# LSM303D.net
KiCad netlist of a schematic drawn in EAGLE
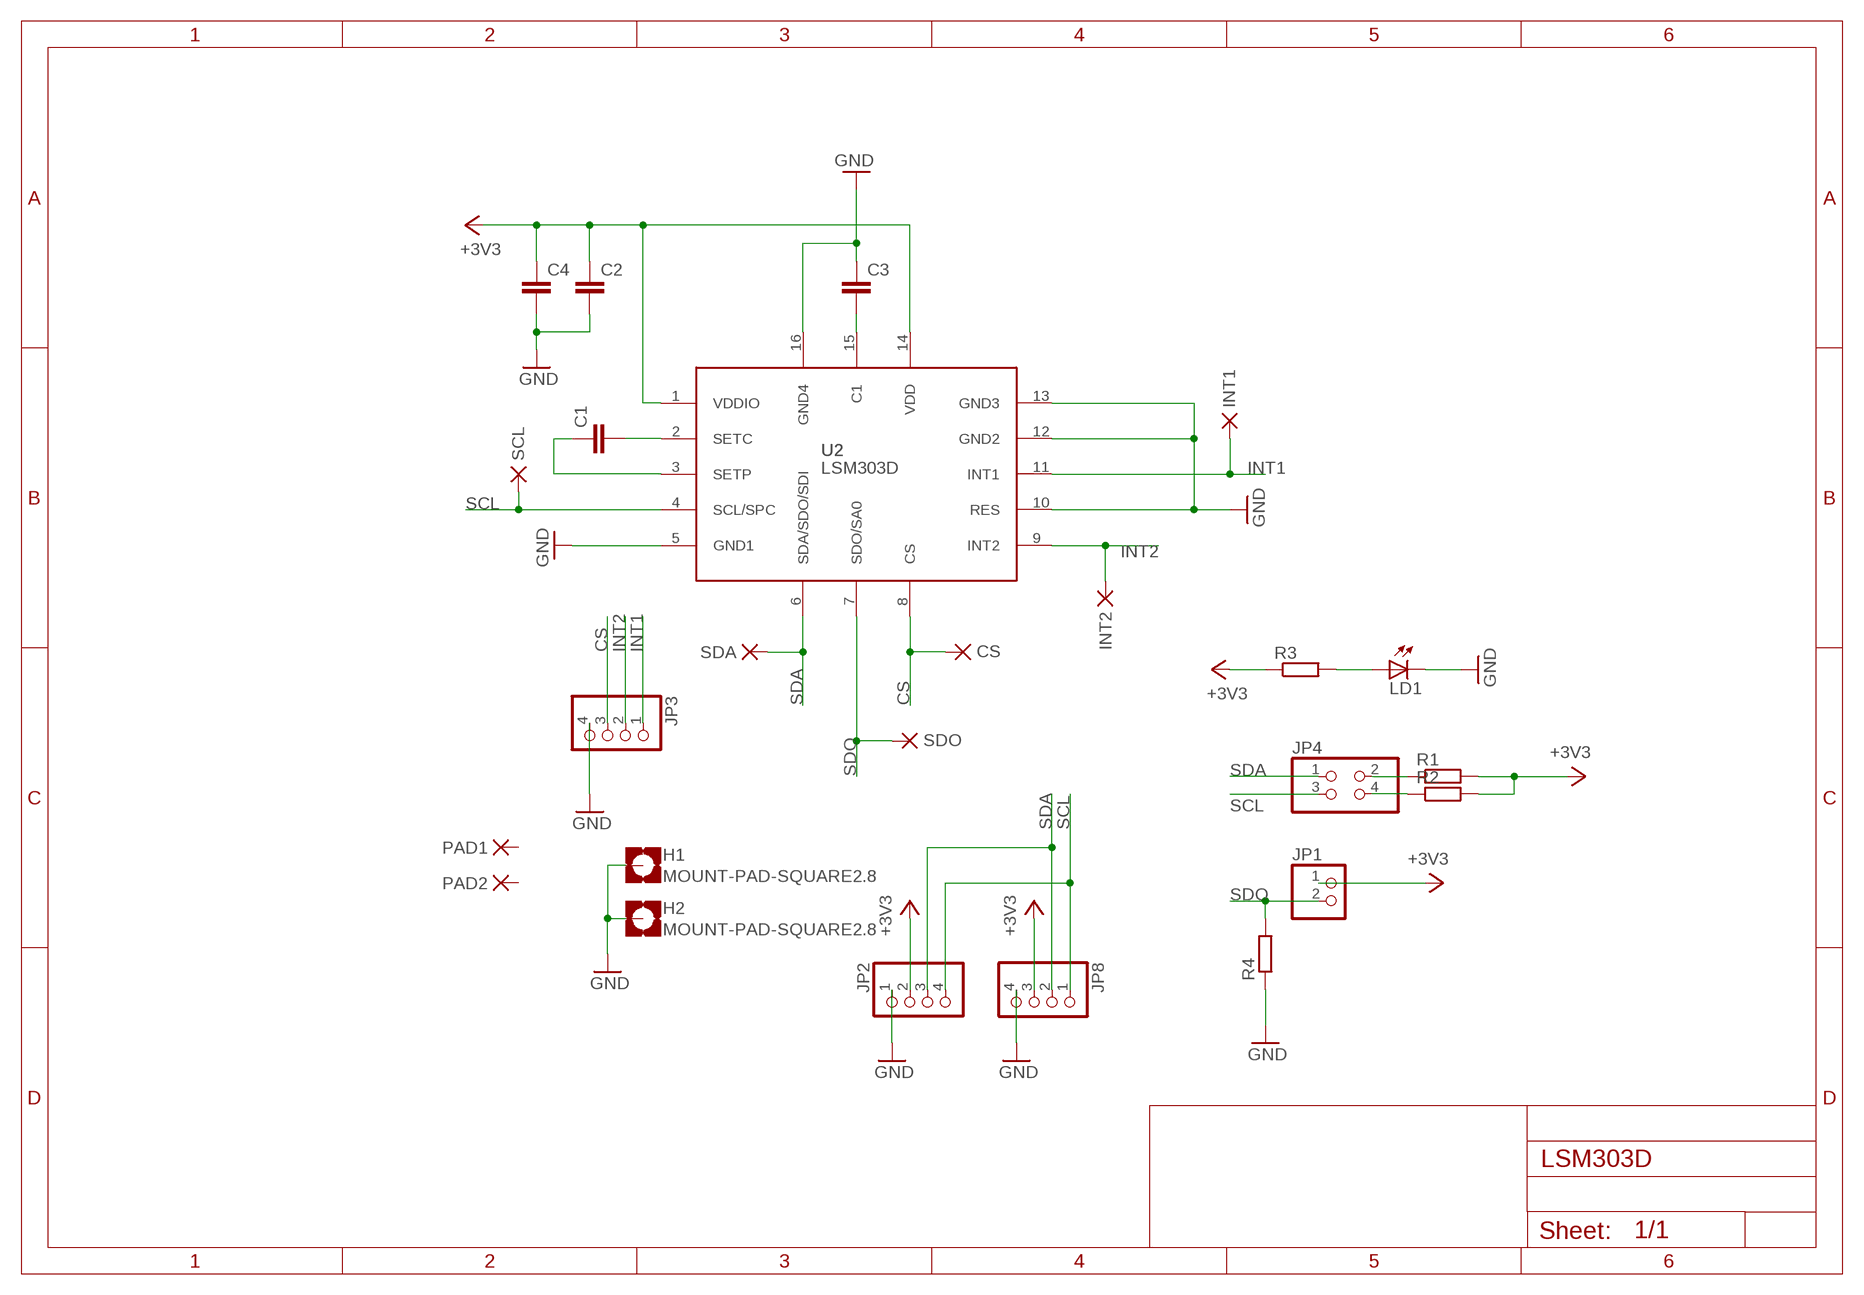
[diagram p0: schematic, sheet 1]

(export (version "E")
  (design (tool "Eeschema 10.0.6"))
  (components
    (comp (ref "C1")
      (value "C-EUC0805")
      (footprint "eagle-import:C0805")
      (libsource (lib "eagle-import") (part "C-EUC0805"))
    )
    (comp (ref "C2")
      (value "C-EUC0805")
      (footprint "eagle-import:C0805")
      (libsource (lib "eagle-import") (part "C-EUC0805"))
    )
    (comp (ref "C3")
      (value "C-EUC0805")
      (footprint "eagle-import:C0805")
      (libsource (lib "eagle-import") (part "C-EUC0805"))
    )
    (comp (ref "C4")
      (value "C-EUC0805")
      (footprint "eagle-import:C0805")
      (libsource (lib "eagle-import") (part "C-EUC0805"))
    )
    (comp (ref "CS")
      (value "PAD-SMD10R")
      (footprint "eagle-import:SMD10R")
      (libsource (lib "eagle-import") (part "PAD-SMD10R"))
    )
    (comp (ref "H1")
      (value "MOUNT-PAD-SQUARE2.8")
      (footprint "eagle-import:2,8-PAD-SQUARE")
      (libsource (lib "eagle-import") (part "MOUNT-PAD-SQUARE2.8"))
    )
    (comp (ref "H2")
      (value "MOUNT-PAD-SQUARE2.8")
      (footprint "eagle-import:2,8-PAD-SQUARE")
      (libsource (lib "eagle-import") (part "MOUNT-PAD-SQUARE2.8"))
    )
    (comp (ref "INT1")
      (value "PAD-SMD10R")
      (footprint "eagle-import:SMD10R")
      (libsource (lib "eagle-import") (part "PAD-SMD10R"))
    )
    (comp (ref "INT2")
      (value "PAD-SMD10R")
      (footprint "eagle-import:SMD10R")
      (libsource (lib "eagle-import") (part "PAD-SMD10R"))
    )
    (comp (ref "JP1")
      (value "PINHD-1X2")
      (footprint "eagle-import:1X02")
      (libsource (lib "eagle-import") (part "PINHD-1X2"))
    )
    (comp (ref "JP2")
      (value "PINHD-1X4_2.54-90°")
      (footprint "eagle-import:1X04_90")
      (libsource (lib "eagle-import") (part "PINHD-1X4_2.54-90°"))
    )
    (comp (ref "JP3")
      (value "PINHD-1X4")
      (footprint "eagle-import:1X04")
      (libsource (lib "eagle-import") (part "PINHD-1X4"))
    )
    (comp (ref "JP4")
      (value "PINHD-2X2_2.54")
      (footprint "eagle-import:2X02")
      (libsource (lib "eagle-import") (part "PINHD-2X2_2.54"))
    )
    (comp (ref "JP8")
      (value "PINHD-1X4_2.54-90°")
      (footprint "eagle-import:1X04_90")
      (libsource (lib "eagle-import") (part "PINHD-1X4_2.54-90°"))
    )
    (comp (ref "LD1")
      (value "LEDCHIPLED_0805")
      (footprint "eagle-import:CHIPLED_0805")
      (libsource (lib "eagle-import") (part "LEDCHIPLED_0805"))
    )
    (comp (ref "PAD1")
      (value "PAD-SMD10R")
      (footprint "eagle-import:SMD10R")
      (libsource (lib "eagle-import") (part "PAD-SMD10R"))
    )
    (comp (ref "PAD2")
      (value "PAD-SMD10R")
      (footprint "eagle-import:SMD10R")
      (libsource (lib "eagle-import") (part "PAD-SMD10R"))
    )
    (comp (ref "R1")
      (value "R-EU_R0805")
      (footprint "eagle-import:R0805")
      (libsource (lib "eagle-import") (part "R-EU_R0805"))
    )
    (comp (ref "R2")
      (value "R-EU_R0805")
      (footprint "eagle-import:R0805")
      (libsource (lib "eagle-import") (part "R-EU_R0805"))
    )
    (comp (ref "R3")
      (value "R-EU_R0805")
      (footprint "eagle-import:R0805")
      (libsource (lib "eagle-import") (part "R-EU_R0805"))
    )
    (comp (ref "R4")
      (value "R-EU_R0805")
      (footprint "eagle-import:R0805")
      (libsource (lib "eagle-import") (part "R-EU_R0805"))
    )
    (comp (ref "SCL")
      (value "PAD-SMD10R")
      (footprint "eagle-import:SMD10R")
      (libsource (lib "eagle-import") (part "PAD-SMD10R"))
    )
    (comp (ref "SDA")
      (value "PAD-SMD10R")
      (footprint "eagle-import:SMD10R")
      (libsource (lib "eagle-import") (part "PAD-SMD10R"))
    )
    (comp (ref "SDO")
      (value "PAD-SMD10R")
      (footprint "eagle-import:SMD10R")
      (libsource (lib "eagle-import") (part "PAD-SMD10R"))
    )
    (comp (ref "U2")
      (value "LSM303D")
      (footprint "eagle-import:LGA16R50P3X5_300X300X100")
      (libsource (lib "eagle-import") (part "LSM303D"))
    )
  )
  (nets
    (net (code "1") (name "+3V3") (class "Default")
      (node (ref "C2") (pin "1") (pinfunction "1_1") (pintype "passive"))
      (node (ref "C4") (pin "1") (pinfunction "1_1") (pintype "passive"))
      (node (ref "JP1") (pin "1") (pinfunction "1_1") (pintype "passive"))
      (node (ref "JP2") (pin "2") (pinfunction "2_2") (pintype "passive"))
      (node (ref "JP8") (pin "3") (pinfunction "3_3") (pintype "passive"))
      (node (ref "R1") (pin "2") (pinfunction "2_2") (pintype "passive"))
      (node (ref "R2") (pin "2") (pinfunction "2_2") (pintype "passive"))
      (node (ref "R3") (pin "1") (pinfunction "1_1") (pintype "passive"))
      (node (ref "U2") (pin "1") (pinfunction "VDDIO_1") (pintype "bidirectional"))
      (node (ref "U2") (pin "14") (pinfunction "VDD_14") (pintype "bidirectional"))
    )
    (net (code "2") (name "/CS") (class "Default")
      (node (ref "CS") (pin "PAD") (pinfunction "P_PAD") (pintype "passive"))
      (node (ref "JP3") (pin "3") (pinfunction "3_3") (pintype "passive"))
      (node (ref "U2") (pin "8") (pinfunction "CS_8") (pintype "bidirectional"))
    )
    (net (code "3") (name "/INT1") (class "Default")
      (node (ref "INT1") (pin "PAD") (pinfunction "P_PAD") (pintype "passive"))
      (node (ref "JP3") (pin "1") (pinfunction "1_1") (pintype "passive"))
      (node (ref "U2") (pin "11") (pinfunction "INT1_11") (pintype "bidirectional"))
    )
    (net (code "4") (name "/INT2") (class "Default")
      (node (ref "INT2") (pin "PAD") (pinfunction "P_PAD") (pintype "passive"))
      (node (ref "JP3") (pin "2") (pinfunction "2_2") (pintype "passive"))
      (node (ref "U2") (pin "9") (pinfunction "INT2_9") (pintype "bidirectional"))
    )
    (net (code "5") (name "/SCL") (class "Default")
      (node (ref "JP2") (pin "4") (pinfunction "4_4") (pintype "passive"))
      (node (ref "JP4") (pin "3") (pinfunction "3_3") (pintype "passive"))
      (node (ref "JP8") (pin "1") (pinfunction "1_1") (pintype "passive"))
      (node (ref "SCL") (pin "PAD") (pinfunction "P_PAD") (pintype "passive"))
      (node (ref "U2") (pin "4") (pinfunction "SCL/SPC_4") (pintype "bidirectional"))
    )
    (net (code "6") (name "/SDA") (class "Default")
      (node (ref "JP2") (pin "3") (pinfunction "3_3") (pintype "passive"))
      (node (ref "JP4") (pin "1") (pinfunction "1_1") (pintype "passive"))
      (node (ref "JP8") (pin "2") (pinfunction "2_2") (pintype "passive"))
      (node (ref "SDA") (pin "PAD") (pinfunction "P_PAD") (pintype "passive"))
      (node (ref "U2") (pin "6") (pinfunction "SDA/SDO/SDI_6") (pintype "bidirectional"))
    )
    (net (code "7") (name "/SDO") (class "Default")
      (node (ref "JP1") (pin "2") (pinfunction "2_2") (pintype "passive"))
      (node (ref "R4") (pin "2") (pinfunction "2_2") (pintype "passive"))
      (node (ref "SDO") (pin "PAD") (pinfunction "P_PAD") (pintype "passive"))
      (node (ref "U2") (pin "7") (pinfunction "SDO/SA0_7") (pintype "bidirectional"))
    )
    (net (code "8") (name "GND") (class "Default")
      (node (ref "C2") (pin "2") (pinfunction "2_2") (pintype "passive"))
      (node (ref "C3") (pin "1") (pinfunction "1_1") (pintype "passive"))
      (node (ref "C4") (pin "2") (pinfunction "2_2") (pintype "passive"))
      (node (ref "H1") (pin "B2,8") (pinfunction "MOUNT_B2,8") (pintype "passive"))
      (node (ref "H2") (pin "B2,8") (pinfunction "MOUNT_B2,8") (pintype "passive"))
      (node (ref "JP2") (pin "1") (pinfunction "1_1") (pintype "passive"))
      (node (ref "JP3") (pin "4") (pinfunction "4_4") (pintype "passive"))
      (node (ref "JP8") (pin "4") (pinfunction "4_4") (pintype "passive"))
      (node (ref "LD1") (pin "C") (pinfunction "C_C") (pintype "passive"))
      (node (ref "R4") (pin "1") (pinfunction "1_1") (pintype "passive"))
      (node (ref "U2") (pin "10") (pinfunction "RES_10") (pintype "bidirectional"))
      (node (ref "U2") (pin "12") (pinfunction "GND2_12") (pintype "bidirectional"))
      (node (ref "U2") (pin "13") (pinfunction "GND3_13") (pintype "bidirectional"))
      (node (ref "U2") (pin "16") (pinfunction "GND4_16") (pintype "bidirectional"))
      (node (ref "U2") (pin "5") (pinfunction "GND1_5") (pintype "bidirectional"))
    )
    (net (code "9") (name "Net-(JP4-Pad2)") (class "Default")
      (node (ref "JP4") (pin "2") (pinfunction "2_2") (pintype "passive"))
      (node (ref "R1") (pin "1") (pinfunction "1_1") (pintype "passive"))
    )
    (net (code "10") (name "Net-(JP4-Pad4)") (class "Default")
      (node (ref "JP4") (pin "4") (pinfunction "4_4") (pintype "passive"))
      (node (ref "R2") (pin "1") (pinfunction "1_1") (pintype "passive"))
    )
    (net (code "11") (name "Net-(LD1-PadA)") (class "Default")
      (node (ref "LD1") (pin "A") (pinfunction "A_A") (pintype "passive"))
      (node (ref "R3") (pin "2") (pinfunction "2_2") (pintype "passive"))
    )
    (net (code "12") (name "Net-(U2-C1)") (class "Default")
      (node (ref "C3") (pin "2") (pinfunction "2_2") (pintype "passive"))
      (node (ref "U2") (pin "15") (pinfunction "C1_15") (pintype "bidirectional"))
    )
    (net (code "13") (name "Net-(U2-SETC)") (class "Default")
      (node (ref "C1") (pin "2") (pinfunction "2_2") (pintype "passive"))
      (node (ref "U2") (pin "2") (pinfunction "SETC_2") (pintype "bidirectional"))
    )
    (net (code "14") (name "Net-(U2-SETP)") (class "Default")
      (node (ref "C1") (pin "1") (pinfunction "1_1") (pintype "passive"))
      (node (ref "U2") (pin "3") (pinfunction "SETP_3") (pintype "bidirectional"))
    )
    (net (code "15") (name "unconnected-(PAD1-P-PadPAD)") (class "Default")
      (node (ref "PAD1") (pin "PAD") (pinfunction "P_PAD") (pintype "passive"))
    )
    (net (code "16") (name "unconnected-(PAD2-P-PadPAD)") (class "Default")
      (node (ref "PAD2") (pin "PAD") (pinfunction "P_PAD") (pintype "passive"))
    )
  )
)
